# tsalledboard.net
KiCad netlist of a schematic drawn in Altium Designer
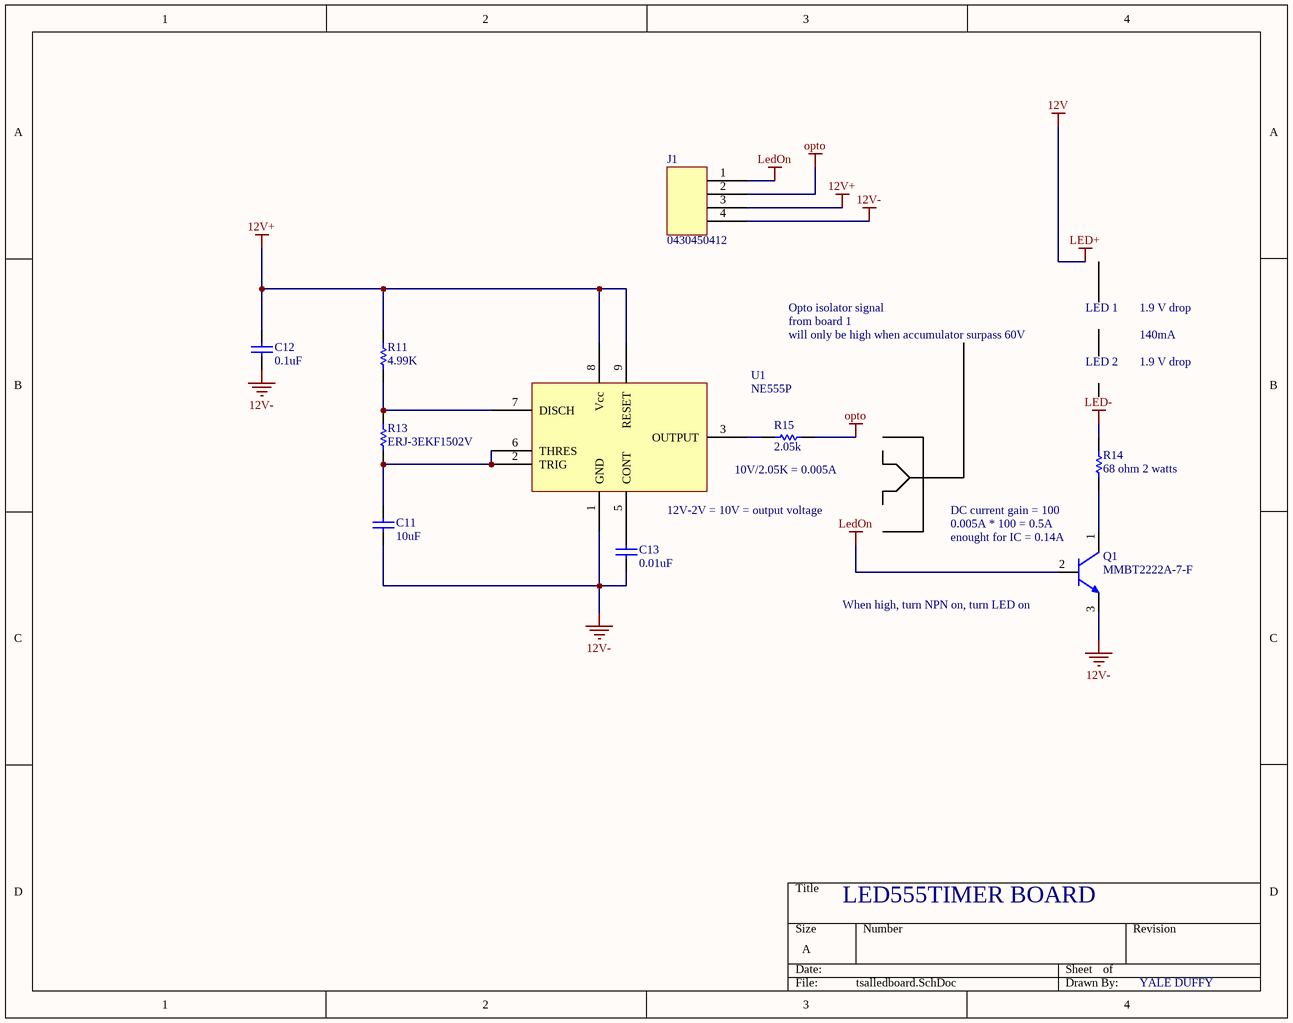
[diagram p0: tsalledboard.SchDoc]

(export (version "E")
  (design (tool "Eeschema 10.0.6"))
  (components
    (comp (ref "C11")
      (value "10uF")
      (footprint "CAPACITOR 0805")
      (description "Capacitor, Ceramic, 10UF 10V X5R 0805")
      (libsource (lib "schematic") (part "C0805C106K8PACTU"))
    )
    (comp (ref "C12")
      (value "0.1uF")
      (footprint "CAP 0402")
      (description "Capacitor 0.1µF ±10% 25V Ceramic X7R 0402 (1005 Metric)")
      (libsource (lib "schematic") (part "C0402C104K3RAC7867"))
    )
    (comp (ref "C13")
      (value "0.01uF")
      (footprint "CAP 1206")
      (description "Capacitor Ceramic 0.011UF 50V C0G/NP0 1206")
      (libsource (lib "schematic") (part "GRM3195C1H113JA01D"))
    )
    (comp (ref "J1")
      (value "0430450412")
      (footprint "0430450412")
      (description "Connector Header Through Hole 4 position 0.118\" (3.00mm)")
      (libsource (lib "schematic") (part "0430450412"))
    )
    (comp (ref "Q1")
      (value "MMBT2222A-7-F")
      (footprint "MMBT2222A")
      (description "Transistor Bipolar NPN 40V 600mA 300MHz 310mW Surface Mount SOT-23-3")
      (libsource (lib "schematic") (part "MMBT2222A-7-F"))
    )
    (comp (ref "R11")
      (value "4.99K")
      (footprint "Resistor 0603")
      (description "Resistor, 4.99k ohms, 0603, SMD")
      (libsource (lib "schematic") (part "ERJ-3EKF4991V"))
    )
    (comp (ref "R13")
      (value "ERJ-3EKF1502V")
      (footprint "Resistor 0603")
      (description "Resistor, 15K ohms, 0603, SMD")
      (libsource (lib "schematic") (part "ERJ-3EKF1502V"))
    )
    (comp (ref "R14")
      (value "68 ohm 2 watts")
      (footprint "CRGP2512F68R")
      (description "Thick Film Resistors - SMD CRGP 2512 68R 1% SMD Resistor")
      (libsource (lib "schematic") (part "CRGP2512F68R"))
    )
    (comp (ref "R15")
      (value "2.05k")
      (footprint "Resistor 0603")
      (description "Resistor, 2.05K ohms, 0603, SMD")
      (libsource (lib "schematic") (part "ERJ-3EKF2051V"))
    )
    (comp (ref "U1")
      (value "NE555P")
      (footprint "NE555P")
      (description "IC, 555 Type, Timer/Oscillator, IC 100kHz 8-PDIP")
      (libsource (lib "schematic") (part "NE555P"))
    )
  )
  (nets
    (net (code "2") (name "12V+") (class "Default")
      (node (ref "C12") (pin "2") (pintype "passive"))
      (node (ref "J1") (pin "3") (pinfunction "3_3") (pintype "passive"))
      (node (ref "R11") (pin "1") (pinfunction "1_1") (pintype "passive"))
      (node (ref "U1") (pin "8") (pinfunction "Vcc_8") (pintype "passive"))
      (node (ref "U1") (pin "9") (pinfunction "RESET_9") (pintype "passive"))
    )
    (net (code "3") (name "12V-") (class "Default")
      (node (ref "C11") (pin "1") (pintype "passive"))
      (node (ref "C12") (pin "1") (pintype "passive"))
      (node (ref "C13") (pin "1") (pintype "passive"))
      (node (ref "J1") (pin "4") (pinfunction "4_4") (pintype "passive"))
      (node (ref "Q1") (pin "3") (pinfunction "E_3") (pintype "passive"))
      (node (ref "U1") (pin "1") (pinfunction "GND_1") (pintype "passive"))
    )
    (net (code "4") (name "LED-") (class "Default")
      (node (ref "R14") (pin "1") (pinfunction "1_1") (pintype "passive"))
    )
    (net (code "5") (name "LedOn") (class "Default")
      (node (ref "J1") (pin "1") (pinfunction "1_1") (pintype "passive"))
      (node (ref "Q1") (pin "2") (pinfunction "B_2") (pintype "passive"))
    )
    (net (code "6") (name "Net-(Q1-C)") (class "Default")
      (node (ref "Q1") (pin "1") (pinfunction "C_1") (pintype "passive"))
      (node (ref "R14") (pin "2") (pinfunction "2_2") (pintype "passive"))
    )
    (net (code "7") (name "Net-(U1-CONT)") (class "Default")
      (node (ref "C13") (pin "2") (pintype "passive"))
      (node (ref "U1") (pin "5") (pinfunction "CONT_5") (pintype "passive"))
    )
    (net (code "8") (name "Net-(U1-DISCH)") (class "Default")
      (node (ref "R11") (pin "2") (pinfunction "2_2") (pintype "passive"))
      (node (ref "R13") (pin "1") (pinfunction "1_1") (pintype "passive"))
      (node (ref "U1") (pin "7") (pinfunction "DISCH_7") (pintype "passive"))
    )
    (net (code "9") (name "Net-(U1-OUTPUT)") (class "Default")
      (node (ref "R15") (pin "1") (pinfunction "1_1") (pintype "passive"))
      (node (ref "U1") (pin "3") (pinfunction "OUTPUT_3") (pintype "passive"))
    )
    (net (code "10") (name "Net-(U1-THRES)") (class "Default")
      (node (ref "C11") (pin "2") (pintype "passive"))
      (node (ref "R13") (pin "2") (pinfunction "2_2") (pintype "passive"))
      (node (ref "U1") (pin "2") (pinfunction "TRIG_2") (pintype "passive"))
      (node (ref "U1") (pin "6") (pinfunction "THRES_6") (pintype "passive"))
    )
    (net (code "11") (name "opto") (class "Default")
      (node (ref "J1") (pin "2") (pinfunction "2_2") (pintype "passive"))
      (node (ref "R15") (pin "2") (pinfunction "2_2") (pintype "passive"))
    )
  )
)
